# FET1.net
KiCad netlist of a schematic drawn in EAGLE
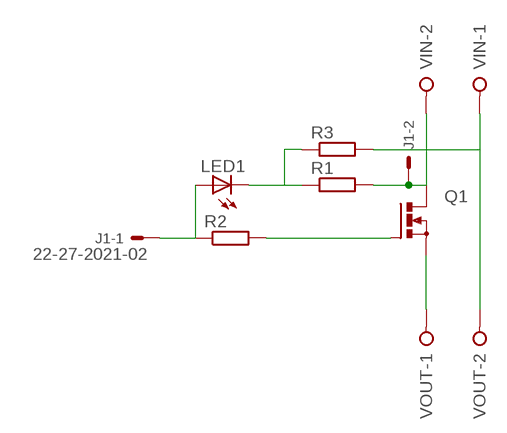
[diagram p0: schematic, sheet 1]

(export (version "E")
  (design (tool "Eeschema 10.0.6"))
  (components
    (comp (ref "J1")
      (value "22-27-2021-02")
      (footprint "eagle-import:6410-02")
      (libsource (lib "eagle-import") (part "22-?-0227-2021"))
    )
    (comp (ref "LED1")
      (value "LED5MM")
      (footprint "eagle-import:LED5MM")
      (libsource (lib "eagle-import") (part "LED5MM"))
    )
    (comp (ref "Q1")
      (value "PMOSFET_NTO220BV")
      (footprint "eagle-import:TO220BV")
      (libsource (lib "eagle-import") (part "PMOSFET_NTO220BV"))
    )
    (comp (ref "R1")
      (value "R-EU_0207/7")
      (footprint "eagle-import:0207_7")
      (libsource (lib "eagle-import") (part "R-EU_0207/7"))
    )
    (comp (ref "R2")
      (value "R-EU_0207/7")
      (footprint "eagle-import:0207_7")
      (libsource (lib "eagle-import") (part "R-EU_0207/7"))
    )
    (comp (ref "R3")
      (value "R-EU_0207/7")
      (footprint "eagle-import:0207_7")
      (libsource (lib "eagle-import") (part "R-EU_0207/7"))
    )
    (comp (ref "VIN")
      (value "W237-02P")
      (footprint "eagle-import:W237-132")
      (libsource (lib "eagle-import") (part "W237-02P"))
    )
    (comp (ref "VOUT")
      (value "W237-02P")
      (footprint "eagle-import:W237-132")
      (libsource (lib "eagle-import") (part "W237-02P"))
    )
  )
  (nets
    (net (code "1") (name "Net-(J1A-S)") (class "Default")
      (node (ref "J1") (pin "1") (pinfunction "S_1") (pintype "passive"))
      (node (ref "LED1") (pin "A") (pinfunction "A_A") (pintype "passive"))
      (node (ref "R2") (pin "1") (pinfunction "1_1") (pintype "passive"))
    )
    (net (code "2") (name "Net-(J1B-S)") (class "Default")
      (node (ref "J1") (pin "2") (pinfunction "S_2") (pintype "passive"))
      (node (ref "Q1") (pin "D") (pinfunction "D_D") (pintype "passive"))
      (node (ref "R1") (pin "2") (pinfunction "2_2") (pintype "passive"))
      (node (ref "VIN") (pin "2") (pinfunction "KL_2") (pintype "passive"))
    )
    (net (code "3") (name "Net-(LED1-C)") (class "Default")
      (node (ref "LED1") (pin "K") (pinfunction "C_K") (pintype "passive"))
      (node (ref "R1") (pin "1") (pinfunction "1_1") (pintype "passive"))
      (node (ref "R3") (pin "1") (pinfunction "1_1") (pintype "passive"))
    )
    (net (code "4") (name "Net-(Q1-PadG)") (class "Default")
      (node (ref "Q1") (pin "G") (pinfunction "G_G") (pintype "passive"))
      (node (ref "R2") (pin "2") (pinfunction "2_2") (pintype "passive"))
    )
    (net (code "5") (name "Net-(VINA-KL)") (class "Default")
      (node (ref "R3") (pin "2") (pinfunction "2_2") (pintype "passive"))
      (node (ref "VIN") (pin "1") (pinfunction "KL_1") (pintype "passive"))
      (node (ref "VOUT") (pin "2") (pinfunction "KL_2") (pintype "passive"))
    )
    (net (code "6") (name "Net-(VOUTA-KL)") (class "Default")
      (node (ref "Q1") (pin "S") (pinfunction "S_S") (pintype "passive"))
      (node (ref "VOUT") (pin "1") (pinfunction "KL_1") (pintype "passive"))
    )
  )
)
